# me433_PCB.net
KiCad netlist of a schematic drawn in EAGLE
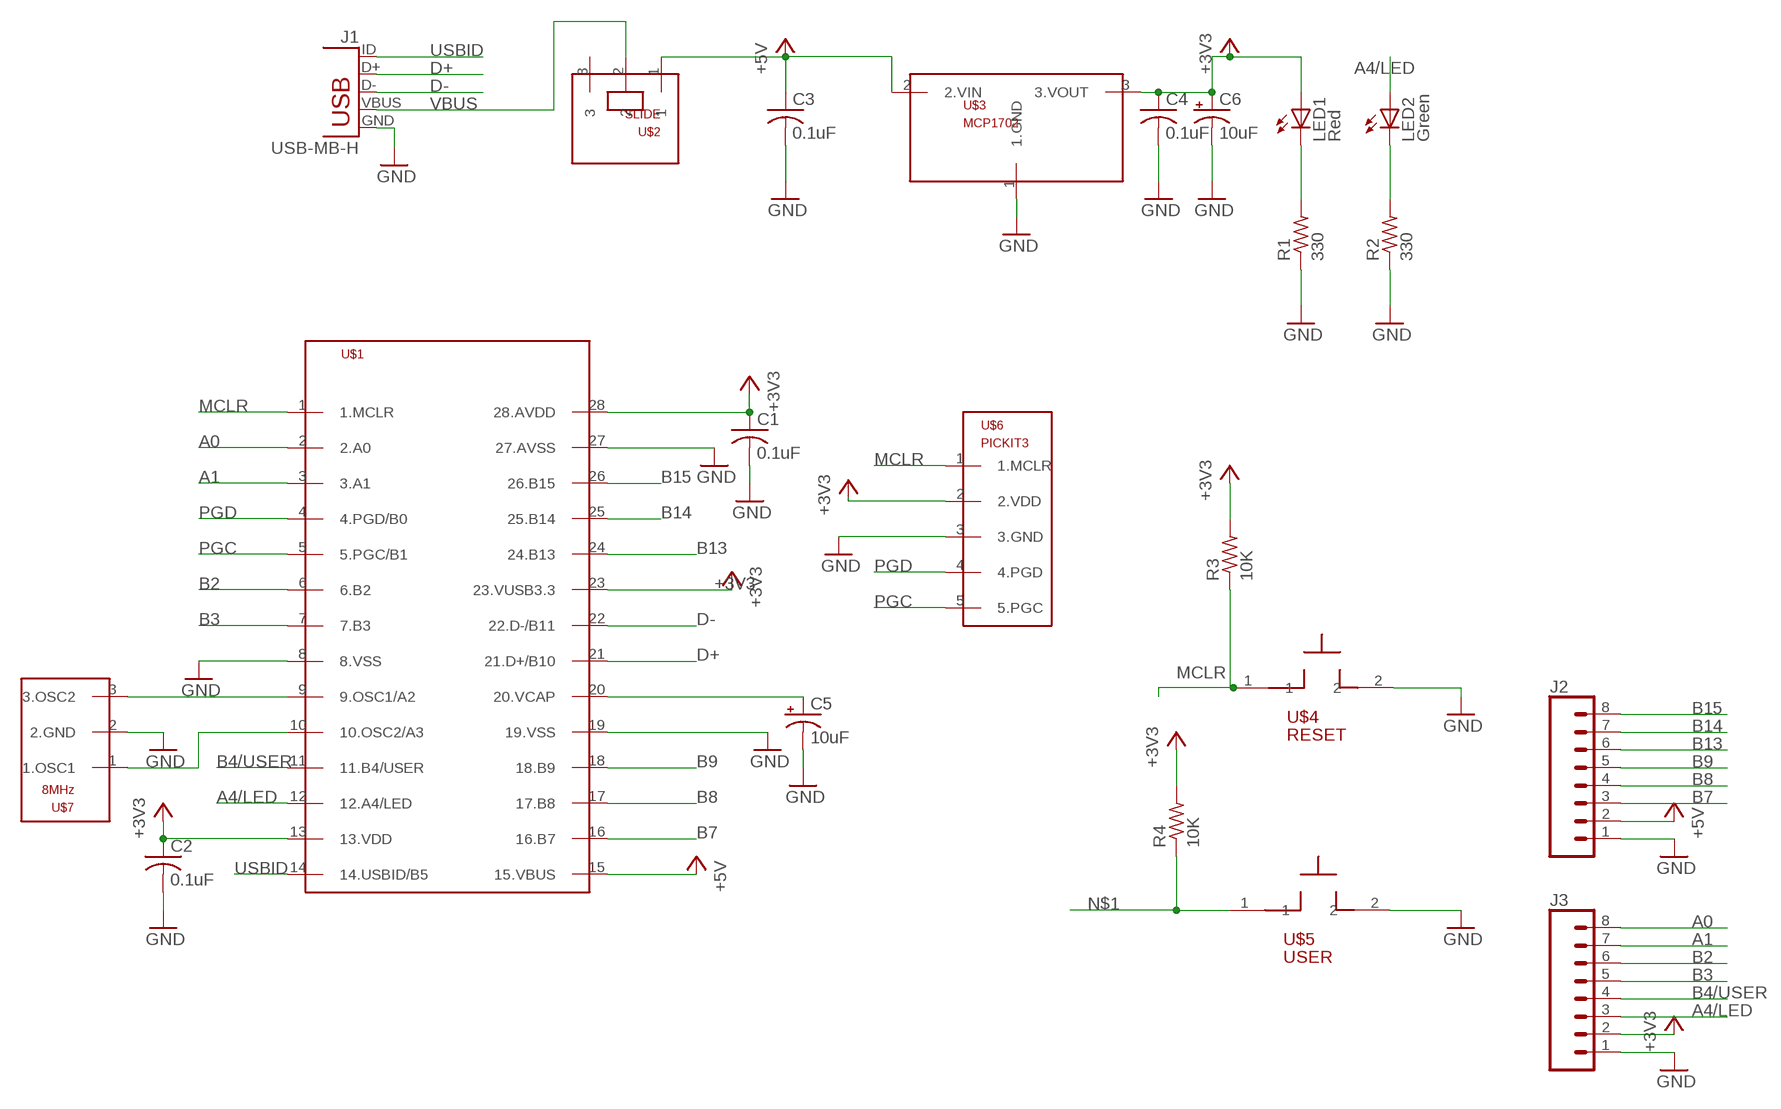
[diagram p0: schematic, sheet 1]

(export (version "E")
  (design (tool "Eeschema 10.0.6"))
  (components
    (comp (ref "C1")
      (value "0.1uF")
      (footprint "eagle-import:C025-025X050")
      (libsource (lib "eagle-import") (part "C-US025-025X050"))
    )
    (comp (ref "C2")
      (value "0.1uF")
      (footprint "eagle-import:C025-025X050")
      (libsource (lib "eagle-import") (part "C-US025-025X050"))
    )
    (comp (ref "C3")
      (value "0.1uF")
      (footprint "eagle-import:C025-025X050")
      (libsource (lib "eagle-import") (part "C-US025-025X050"))
    )
    (comp (ref "C4")
      (value "0.1uF")
      (footprint "eagle-import:C025-025X050")
      (libsource (lib "eagle-import") (part "C-US025-025X050"))
    )
    (comp (ref "C5")
      (value "10uF")
      (footprint "eagle-import:B45181B")
      (libsource (lib "eagle-import") (part "CPOL-USB45181B"))
    )
    (comp (ref "C6")
      (value "10uF")
      (footprint "eagle-import:B45181B")
      (libsource (lib "eagle-import") (part "CPOL-USB45181B"))
    )
    (comp (ref "J1")
      (value "USB-MB-H")
      (footprint "eagle-import:USB-MB-H")
      (libsource (lib "eagle-import") (part "USB-MB-H"))
    )
    (comp (ref "J2")
      (value "CONN_08\"")
      (footprint "eagle-import:1X08")
      (libsource (lib "eagle-import") (part "CONN_08{dblquote}"))
    )
    (comp (ref "J3")
      (value "CONN_08\"")
      (footprint "eagle-import:1X08")
      (libsource (lib "eagle-import") (part "CONN_08{dblquote}"))
    )
    (comp (ref "LED1")
      (value "Red")
      (footprint "eagle-import:LED3MM")
      (libsource (lib "eagle-import") (part "LED3MM"))
    )
    (comp (ref "LED2")
      (value "Green")
      (footprint "eagle-import:LED3MM")
      (libsource (lib "eagle-import") (part "LED3MM"))
    )
    (comp (ref "R1")
      (value "330")
      (footprint "eagle-import:0207_10")
      (libsource (lib "eagle-import") (part "R-US_0207/10"))
    )
    (comp (ref "R2")
      (value "330")
      (footprint "eagle-import:0207_10")
      (libsource (lib "eagle-import") (part "R-US_0207/10"))
    )
    (comp (ref "R3")
      (value "10K")
      (footprint "eagle-import:0207_10")
      (libsource (lib "eagle-import") (part "R-US_0207/10"))
    )
    (comp (ref "R4")
      (value "10K")
      (footprint "eagle-import:0207_10")
      (libsource (lib "eagle-import") (part "R-US_0207/10"))
    )
    (comp (ref "U$1")
      (value "PIC32MX250F138B")
      (footprint "eagle-import:DIL28-3")
      (libsource (lib "eagle-import") (part "PIC32MX250F138B"))
    )
    (comp (ref "U$2")
      (value "SLIDE")
      (footprint "eagle-import:SLIDE")
      (libsource (lib "eagle-import") (part "SLIDE"))
    )
    (comp (ref "U$3")
      (value "MCP1702")
      (footprint "eagle-import:TO92")
      (libsource (lib "eagle-import") (part "MCP1702"))
    )
    (comp (ref "U$4")
      (value "RESET")
      (footprint "eagle-import:PB")
      (libsource (lib "eagle-import") (part "PB"))
    )
    (comp (ref "U$5")
      (value "USER")
      (footprint "eagle-import:PB")
      (libsource (lib "eagle-import") (part "PB"))
    )
    (comp (ref "U$6")
      (value "PICKIT3")
      (footprint "eagle-import:1X05")
      (libsource (lib "eagle-import") (part "PICKIT3"))
    )
    (comp (ref "U$7")
      (value "8MHz")
      (footprint "eagle-import:OSC")
      (libsource (lib "eagle-import") (part "OSC"))
    )
  )
  (nets
    (net (code "1") (name "+3V3") (class "Default")
      (node (ref "C1") (pin "1") (pinfunction "1_1") (pintype "passive"))
      (node (ref "C2") (pin "1") (pinfunction "1_1") (pintype "passive"))
      (node (ref "C4") (pin "1") (pinfunction "1_1") (pintype "passive"))
      (node (ref "C6") (pin "+") (pinfunction "+_+") (pintype "passive"))
      (node (ref "J3") (pin "2") (pinfunction "2_2") (pintype "passive"))
      (node (ref "LED1") (pin "A") (pinfunction "A_A") (pintype "passive"))
      (node (ref "R3") (pin "2") (pinfunction "2_2") (pintype "passive"))
      (node (ref "R4") (pin "2") (pinfunction "2_2") (pintype "passive"))
      (node (ref "U$1") (pin "13") (pinfunction "13.VDD_13") (pintype "bidirectional"))
      (node (ref "U$1") (pin "23") (pinfunction "23.VUSB3.3_23") (pintype "bidirectional"))
      (node (ref "U$1") (pin "28") (pinfunction "28.AVDD_28") (pintype "bidirectional"))
      (node (ref "U$3") (pin "3") (pinfunction "3.VOUT_3") (pintype "bidirectional"))
      (node (ref "U$6") (pin "2") (pinfunction "2.VDD_2") (pintype "bidirectional"))
    )
    (net (code "2") (name "+5V") (class "Default")
      (node (ref "C3") (pin "1") (pinfunction "1_1") (pintype "passive"))
      (node (ref "J2") (pin "2") (pinfunction "2_2") (pintype "passive"))
      (node (ref "U$1") (pin "15") (pinfunction "15.VBUS_15") (pintype "bidirectional"))
      (node (ref "U$2") (pin "1") (pinfunction "1_1") (pintype "bidirectional"))
      (node (ref "U$3") (pin "2") (pinfunction "2.VIN_2") (pintype "bidirectional"))
    )
    (net (code "3") (name "/A0") (class "Default")
      (node (ref "J3") (pin "8") (pinfunction "8_8") (pintype "passive"))
      (node (ref "U$1") (pin "2") (pinfunction "2.A0_2") (pintype "bidirectional"))
    )
    (net (code "4") (name "/A1") (class "Default")
      (node (ref "J3") (pin "7") (pinfunction "7_7") (pintype "passive"))
      (node (ref "U$1") (pin "3") (pinfunction "3.A1_3") (pintype "bidirectional"))
    )
    (net (code "5") (name "/A4{slash}LED") (class "Default")
      (node (ref "J3") (pin "3") (pinfunction "3_3") (pintype "passive"))
      (node (ref "LED2") (pin "A") (pinfunction "A_A") (pintype "passive"))
      (node (ref "U$1") (pin "12") (pinfunction "12.A4/LED_12") (pintype "bidirectional"))
    )
    (net (code "6") (name "/B2") (class "Default")
      (node (ref "J3") (pin "6") (pinfunction "6_6") (pintype "passive"))
      (node (ref "U$1") (pin "6") (pinfunction "6.B2_6") (pintype "bidirectional"))
    )
    (net (code "7") (name "/B3") (class "Default")
      (node (ref "J3") (pin "5") (pinfunction "5_5") (pintype "passive"))
      (node (ref "U$1") (pin "7") (pinfunction "7.B3_7") (pintype "bidirectional"))
    )
    (net (code "8") (name "/B4{slash}USER") (class "Default")
      (node (ref "J3") (pin "4") (pinfunction "4_4") (pintype "passive"))
      (node (ref "U$1") (pin "11") (pinfunction "11.B4/USER_11") (pintype "bidirectional"))
    )
    (net (code "9") (name "/B7") (class "Default")
      (node (ref "J2") (pin "3") (pinfunction "3_3") (pintype "passive"))
      (node (ref "U$1") (pin "16") (pinfunction "16.B7_16") (pintype "bidirectional"))
    )
    (net (code "10") (name "/B8") (class "Default")
      (node (ref "J2") (pin "4") (pinfunction "4_4") (pintype "passive"))
      (node (ref "U$1") (pin "17") (pinfunction "17.B8_17") (pintype "bidirectional"))
    )
    (net (code "11") (name "/B9") (class "Default")
      (node (ref "J2") (pin "5") (pinfunction "5_5") (pintype "passive"))
      (node (ref "U$1") (pin "18") (pinfunction "18.B9_18") (pintype "bidirectional"))
    )
    (net (code "12") (name "/B13") (class "Default")
      (node (ref "J2") (pin "6") (pinfunction "6_6") (pintype "passive"))
      (node (ref "U$1") (pin "24") (pinfunction "24.B13_24") (pintype "bidirectional"))
    )
    (net (code "13") (name "/B14") (class "Default")
      (node (ref "J2") (pin "7") (pinfunction "7_7") (pintype "passive"))
      (node (ref "U$1") (pin "25") (pinfunction "25.B14_25") (pintype "bidirectional"))
    )
    (net (code "14") (name "/B15") (class "Default")
      (node (ref "J2") (pin "8") (pinfunction "8_8") (pintype "passive"))
      (node (ref "U$1") (pin "26") (pinfunction "26.B15_26") (pintype "bidirectional"))
    )
    (net (code "15") (name "/D+") (class "Default")
      (node (ref "J1") (pin "D+") (pinfunction "D+_D+") (pintype "bidirectional"))
      (node (ref "U$1") (pin "21") (pinfunction "21.D+/B10_21") (pintype "bidirectional"))
    )
    (net (code "16") (name "/D-") (class "Default")
      (node (ref "J1") (pin "D-") (pinfunction "D-_D-") (pintype "bidirectional"))
      (node (ref "U$1") (pin "22") (pinfunction "22.D-/B11_22") (pintype "bidirectional"))
    )
    (net (code "17") (name "/MCLR") (class "Default")
      (node (ref "R3") (pin "1") (pinfunction "1_1") (pintype "passive"))
      (node (ref "U$1") (pin "1") (pinfunction "1.MCLR_1") (pintype "bidirectional"))
      (node (ref "U$4") (pin "1") (pinfunction "1_1") (pintype "bidirectional"))
      (node (ref "U$6") (pin "1") (pinfunction "1.MCLR_1") (pintype "bidirectional"))
    )
    (net (code "18") (name "/N$1") (class "Default")
      (node (ref "R4") (pin "1") (pinfunction "1_1") (pintype "passive"))
      (node (ref "U$5") (pin "1") (pinfunction "1_1") (pintype "bidirectional"))
    )
    (net (code "19") (name "/PGC") (class "Default")
      (node (ref "U$1") (pin "5") (pinfunction "5.PGC/B1_5") (pintype "bidirectional"))
      (node (ref "U$6") (pin "5") (pinfunction "5.PGC_5") (pintype "bidirectional"))
    )
    (net (code "20") (name "/PGD") (class "Default")
      (node (ref "U$1") (pin "4") (pinfunction "4.PGD/B0_4") (pintype "bidirectional"))
      (node (ref "U$6") (pin "4") (pinfunction "4.PGD_4") (pintype "bidirectional"))
    )
    (net (code "21") (name "/USBID") (class "Default")
      (node (ref "J1") (pin "ID") (pinfunction "ID_ID") (pintype "bidirectional"))
      (node (ref "U$1") (pin "14") (pinfunction "14.USBID/B5_14") (pintype "bidirectional"))
    )
    (net (code "22") (name "/VBUS") (class "Default")
      (node (ref "J1") (pin "VBUS") (pinfunction "VBUS_VBUS") (pintype "bidirectional"))
      (node (ref "U$2") (pin "2") (pinfunction "2_2") (pintype "bidirectional"))
    )
    (net (code "23") (name "GND") (class "Default")
      (node (ref "C1") (pin "2") (pinfunction "2_2") (pintype "passive"))
      (node (ref "C2") (pin "2") (pinfunction "2_2") (pintype "passive"))
      (node (ref "C3") (pin "2") (pinfunction "2_2") (pintype "passive"))
      (node (ref "C4") (pin "2") (pinfunction "2_2") (pintype "passive"))
      (node (ref "C5") (pin "-") (pinfunction "-_-") (pintype "passive"))
      (node (ref "C6") (pin "-") (pinfunction "-_-") (pintype "passive"))
      (node (ref "J1") (pin "GND") (pinfunction "GND_GND") (pintype "bidirectional"))
      (node (ref "J2") (pin "1") (pinfunction "1_1") (pintype "passive"))
      (node (ref "J3") (pin "1") (pinfunction "1_1") (pintype "passive"))
      (node (ref "R1") (pin "1") (pinfunction "1_1") (pintype "passive"))
      (node (ref "R2") (pin "1") (pinfunction "1_1") (pintype "passive"))
      (node (ref "U$1") (pin "19") (pinfunction "19.VSS_19") (pintype "bidirectional"))
      (node (ref "U$1") (pin "27") (pinfunction "27.AVSS_27") (pintype "bidirectional"))
      (node (ref "U$1") (pin "8") (pinfunction "8.VSS_8") (pintype "bidirectional"))
      (node (ref "U$3") (pin "1") (pinfunction "1.GND_1") (pintype "bidirectional"))
      (node (ref "U$4") (pin "2") (pinfunction "2_2") (pintype "bidirectional"))
      (node (ref "U$5") (pin "2") (pinfunction "2_2") (pintype "bidirectional"))
      (node (ref "U$6") (pin "3") (pinfunction "3.GND_3") (pintype "bidirectional"))
      (node (ref "U$7") (pin "2") (pinfunction "2.GND_2") (pintype "bidirectional"))
    )
    (net (code "24") (name "Net-(LED1-C)") (class "Default")
      (node (ref "LED1") (pin "K") (pinfunction "C_K") (pintype "passive"))
      (node (ref "R1") (pin "2") (pinfunction "2_2") (pintype "passive"))
    )
    (net (code "25") (name "Net-(LED2-C)") (class "Default")
      (node (ref "LED2") (pin "K") (pinfunction "C_K") (pintype "passive"))
      (node (ref "R2") (pin "2") (pinfunction "2_2") (pintype "passive"))
    )
    (net (code "26") (name "Net-(U$1-9.OSC1{slash}A2)") (class "Default")
      (node (ref "U$1") (pin "9") (pinfunction "9.OSC1/A2_9") (pintype "bidirectional"))
      (node (ref "U$7") (pin "3") (pinfunction "3.OSC2_3") (pintype "bidirectional"))
    )
    (net (code "27") (name "Net-(U$1-10.OSC2{slash}A3)") (class "Default")
      (node (ref "U$1") (pin "10") (pinfunction "10.OSC2/A3_10") (pintype "bidirectional"))
      (node (ref "U$7") (pin "1") (pinfunction "1.OSC1_1") (pintype "bidirectional"))
    )
    (net (code "28") (name "Net-(U$1-20.VCAP)") (class "Default")
      (node (ref "C5") (pin "+") (pinfunction "+_+") (pintype "passive"))
      (node (ref "U$1") (pin "20") (pinfunction "20.VCAP_20") (pintype "bidirectional"))
    )
    (net (code "29") (name "unconnected-(U$2-Pad3)") (class "Default")
      (node (ref "U$2") (pin "3") (pinfunction "3_3") (pintype "bidirectional"))
    )
  )
)
